# M240X.net
KiCad netlist of a schematic drawn in EAGLE
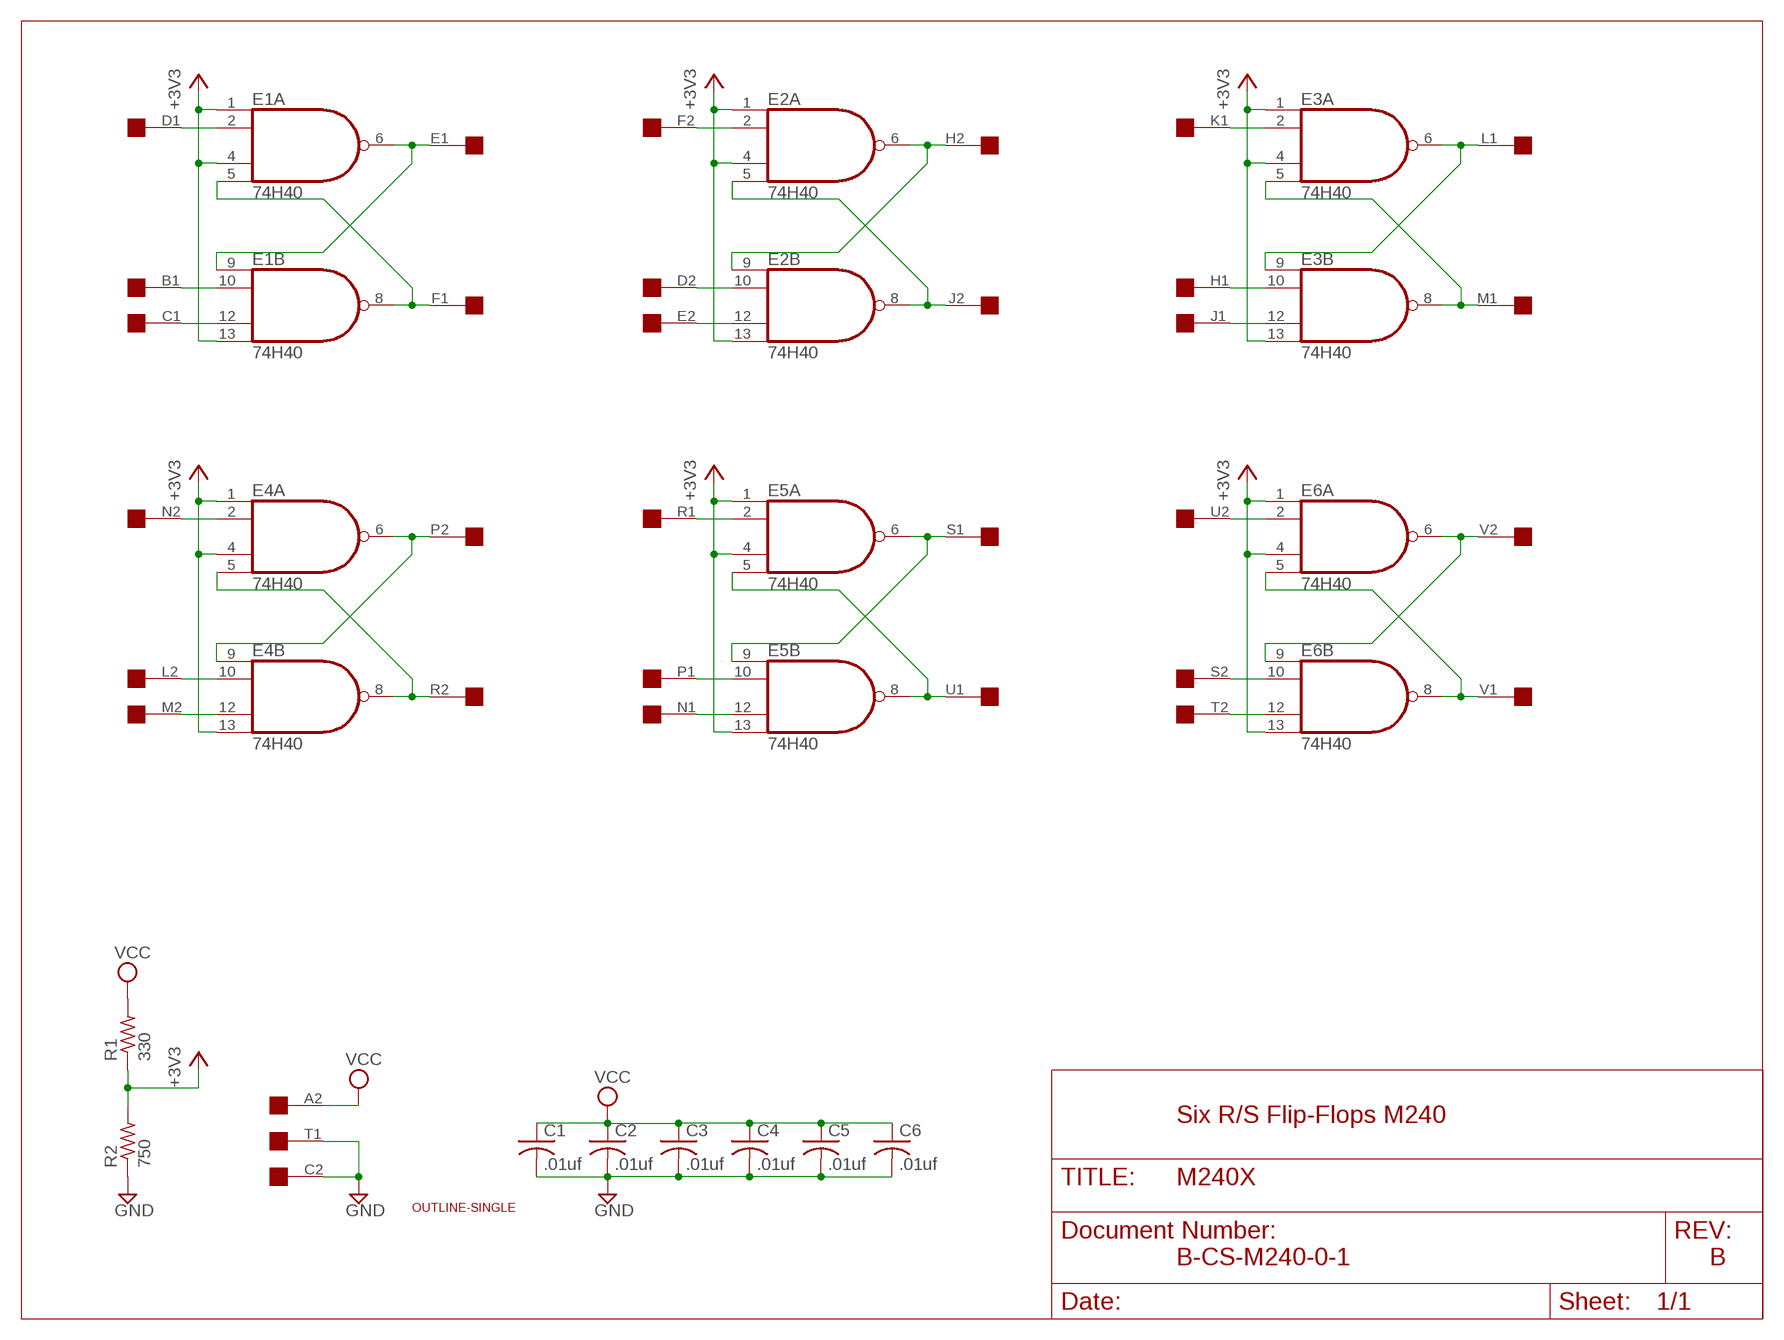
[diagram p0: schematic, sheet 1]

(export (version "E")
  (design (tool "Eeschema 10.0.6"))
  (components
    (comp (ref "C1")
      (value ".01uf")
      (footprint "eagle-import:C050-025X075")
      (libsource (lib "eagle-import") (part "C-US050-025X075"))
    )
    (comp (ref "C2")
      (value ".01uf")
      (footprint "eagle-import:C050-025X075")
      (libsource (lib "eagle-import") (part "C-US050-025X075"))
    )
    (comp (ref "C3")
      (value ".01uf")
      (footprint "eagle-import:C050-025X075")
      (libsource (lib "eagle-import") (part "C-US050-025X075"))
    )
    (comp (ref "C4")
      (value ".01uf")
      (footprint "eagle-import:C050-025X075")
      (libsource (lib "eagle-import") (part "C-US050-025X075"))
    )
    (comp (ref "C5")
      (value ".01uf")
      (footprint "eagle-import:C050-025X075")
      (libsource (lib "eagle-import") (part "C-US050-025X075"))
    )
    (comp (ref "C6")
      (value ".01uf")
      (footprint "eagle-import:C050-025X075")
      (libsource (lib "eagle-import") (part "C-US050-025X075"))
    )
    (comp (ref "E1")
      (value "74H40")
      (footprint "eagle-import:DIL14")
      (libsource (lib "eagle-import") (part "7420NS"))
    )
    (comp (ref "E2")
      (value "74H40")
      (footprint "eagle-import:DIL14")
      (libsource (lib "eagle-import") (part "7420NS"))
    )
    (comp (ref "E3")
      (value "74H40")
      (footprint "eagle-import:DIL14")
      (libsource (lib "eagle-import") (part "7420NS"))
    )
    (comp (ref "E4")
      (value "74H40")
      (footprint "eagle-import:DIL14")
      (libsource (lib "eagle-import") (part "7420NS"))
    )
    (comp (ref "E5")
      (value "74H40")
      (footprint "eagle-import:DIL14")
      (libsource (lib "eagle-import") (part "7420NS"))
    )
    (comp (ref "E6")
      (value "74H40")
      (footprint "eagle-import:DIL14")
      (libsource (lib "eagle-import") (part "7420NS"))
    )
    (comp (ref "R1")
      (value "330")
      (footprint "eagle-import:0207_10")
      (libsource (lib "eagle-import") (part "R-US_0207/10"))
    )
    (comp (ref "R2")
      (value "750")
      (footprint "eagle-import:0207_10")
      (libsource (lib "eagle-import") (part "R-US_0207/10"))
    )
    (comp (ref "U$1")
      (value "OUTLINE-SINGLE")
      (footprint "eagle-import:SINGLE")
      (libsource (lib "eagle-import") (part "OUTLINE-SINGLE"))
    )
    (comp (ref "U$4")
      (value "SINGLE")
      (footprint "eagle-import:EDGE-CON2")
      (libsource (lib "eagle-import") (part "SINGLE"))
    )
  )
  (nets
    (net (code "1") (name "+3V3") (class "Default")
      (node (ref "E1") (pin "1") (pinfunction "I0_1") (pintype "input"))
      (node (ref "E1") (pin "13") (pinfunction "I3_13") (pintype "input"))
      (node (ref "E1") (pin "4") (pinfunction "I2_4") (pintype "input"))
      (node (ref "E2") (pin "1") (pinfunction "I0_1") (pintype "input"))
      (node (ref "E2") (pin "13") (pinfunction "I3_13") (pintype "input"))
      (node (ref "E2") (pin "4") (pinfunction "I2_4") (pintype "input"))
      (node (ref "E3") (pin "1") (pinfunction "I0_1") (pintype "input"))
      (node (ref "E3") (pin "13") (pinfunction "I3_13") (pintype "input"))
      (node (ref "E3") (pin "4") (pinfunction "I2_4") (pintype "input"))
      (node (ref "E4") (pin "1") (pinfunction "I0_1") (pintype "input"))
      (node (ref "E4") (pin "13") (pinfunction "I3_13") (pintype "input"))
      (node (ref "E4") (pin "4") (pinfunction "I2_4") (pintype "input"))
      (node (ref "E5") (pin "1") (pinfunction "I0_1") (pintype "input"))
      (node (ref "E5") (pin "13") (pinfunction "I3_13") (pintype "input"))
      (node (ref "E5") (pin "4") (pinfunction "I2_4") (pintype "input"))
      (node (ref "E6") (pin "1") (pinfunction "I0_1") (pintype "input"))
      (node (ref "E6") (pin "13") (pinfunction "I3_13") (pintype "input"))
      (node (ref "E6") (pin "4") (pinfunction "I2_4") (pintype "input"))
      (node (ref "R1") (pin "1") (pinfunction "1_1") (pintype "passive"))
      (node (ref "R2") (pin "2") (pinfunction "2_2") (pintype "passive"))
    )
    (net (code "2") (name "GND") (class "Default")
      (node (ref "C1") (pin "2") (pinfunction "2_2") (pintype "passive"))
      (node (ref "C2") (pin "2") (pinfunction "2_2") (pintype "passive"))
      (node (ref "C3") (pin "2") (pinfunction "2_2") (pintype "passive"))
      (node (ref "C4") (pin "2") (pinfunction "2_2") (pintype "passive"))
      (node (ref "C5") (pin "2") (pinfunction "2_2") (pintype "passive"))
      (node (ref "C6") (pin "2") (pinfunction "2_2") (pintype "passive"))
      (node (ref "R2") (pin "1") (pinfunction "1_1") (pintype "passive"))
      (node (ref "U$4") (pin "C2") (pinfunction "1_C2") (pintype "bidirectional"))
      (node (ref "U$4") (pin "T1") (pinfunction "1_T1") (pintype "bidirectional"))
    )
    (net (code "3") (name "Net-(E1A-I1)") (class "Default")
      (node (ref "E1") (pin "2") (pinfunction "I1_2") (pintype "input"))
      (node (ref "U$4") (pin "D1") (pinfunction "1_D1") (pintype "bidirectional"))
    )
    (net (code "4") (name "Net-(E1A-I3)") (class "Default")
      (node (ref "E1") (pin "5") (pinfunction "I3_5") (pintype "input"))
      (node (ref "E1") (pin "8") (pinfunction "O_8") (pintype "output"))
      (node (ref "U$4") (pin "F1") (pinfunction "1_F1") (pintype "bidirectional"))
    )
    (net (code "5") (name "Net-(E1A-O)") (class "Default")
      (node (ref "E1") (pin "6") (pinfunction "O_6") (pintype "output"))
      (node (ref "E1") (pin "9") (pinfunction "I0_9") (pintype "input"))
      (node (ref "U$4") (pin "E1") (pinfunction "1_E1") (pintype "bidirectional"))
    )
    (net (code "6") (name "Net-(E1B-I1)") (class "Default")
      (node (ref "E1") (pin "10") (pinfunction "I1_10") (pintype "input"))
      (node (ref "U$4") (pin "B1") (pinfunction "1_B1") (pintype "bidirectional"))
    )
    (net (code "7") (name "Net-(E1B-I2)") (class "Default")
      (node (ref "E1") (pin "12") (pinfunction "I2_12") (pintype "input"))
      (node (ref "U$4") (pin "C1") (pinfunction "1_C1") (pintype "bidirectional"))
    )
    (net (code "8") (name "Net-(E2A-I1)") (class "Default")
      (node (ref "E2") (pin "2") (pinfunction "I1_2") (pintype "input"))
      (node (ref "U$4") (pin "F2") (pinfunction "1_F2") (pintype "bidirectional"))
    )
    (net (code "9") (name "Net-(E2A-I3)") (class "Default")
      (node (ref "E2") (pin "5") (pinfunction "I3_5") (pintype "input"))
      (node (ref "E2") (pin "8") (pinfunction "O_8") (pintype "output"))
      (node (ref "U$4") (pin "J2") (pinfunction "1_J2") (pintype "bidirectional"))
    )
    (net (code "10") (name "Net-(E2A-O)") (class "Default")
      (node (ref "E2") (pin "6") (pinfunction "O_6") (pintype "output"))
      (node (ref "E2") (pin "9") (pinfunction "I0_9") (pintype "input"))
      (node (ref "U$4") (pin "H2") (pinfunction "1_H2") (pintype "bidirectional"))
    )
    (net (code "11") (name "Net-(E2B-I1)") (class "Default")
      (node (ref "E2") (pin "10") (pinfunction "I1_10") (pintype "input"))
      (node (ref "U$4") (pin "D2") (pinfunction "1_D2") (pintype "bidirectional"))
    )
    (net (code "12") (name "Net-(E2B-I2)") (class "Default")
      (node (ref "E2") (pin "12") (pinfunction "I2_12") (pintype "input"))
      (node (ref "U$4") (pin "E2") (pinfunction "1_E2") (pintype "bidirectional"))
    )
    (net (code "13") (name "Net-(E3A-I1)") (class "Default")
      (node (ref "E3") (pin "2") (pinfunction "I1_2") (pintype "input"))
      (node (ref "U$4") (pin "K1") (pinfunction "1_K1") (pintype "bidirectional"))
    )
    (net (code "14") (name "Net-(E3A-I3)") (class "Default")
      (node (ref "E3") (pin "5") (pinfunction "I3_5") (pintype "input"))
      (node (ref "E3") (pin "8") (pinfunction "O_8") (pintype "output"))
      (node (ref "U$4") (pin "M1") (pinfunction "1_M1") (pintype "bidirectional"))
    )
    (net (code "15") (name "Net-(E3A-O)") (class "Default")
      (node (ref "E3") (pin "6") (pinfunction "O_6") (pintype "output"))
      (node (ref "E3") (pin "9") (pinfunction "I0_9") (pintype "input"))
      (node (ref "U$4") (pin "L1") (pinfunction "1_L1") (pintype "bidirectional"))
    )
    (net (code "16") (name "Net-(E3B-I1)") (class "Default")
      (node (ref "E3") (pin "10") (pinfunction "I1_10") (pintype "input"))
      (node (ref "U$4") (pin "H1") (pinfunction "1_H1") (pintype "bidirectional"))
    )
    (net (code "17") (name "Net-(E3B-I2)") (class "Default")
      (node (ref "E3") (pin "12") (pinfunction "I2_12") (pintype "input"))
      (node (ref "U$4") (pin "J1") (pinfunction "1_J1") (pintype "bidirectional"))
    )
    (net (code "18") (name "Net-(E4A-I1)") (class "Default")
      (node (ref "E4") (pin "2") (pinfunction "I1_2") (pintype "input"))
      (node (ref "U$4") (pin "N2") (pinfunction "1_N2") (pintype "bidirectional"))
    )
    (net (code "19") (name "Net-(E4A-I3)") (class "Default")
      (node (ref "E4") (pin "5") (pinfunction "I3_5") (pintype "input"))
      (node (ref "E4") (pin "8") (pinfunction "O_8") (pintype "output"))
      (node (ref "U$4") (pin "R2") (pinfunction "1_R2") (pintype "bidirectional"))
    )
    (net (code "20") (name "Net-(E4A-O)") (class "Default")
      (node (ref "E4") (pin "6") (pinfunction "O_6") (pintype "output"))
      (node (ref "E4") (pin "9") (pinfunction "I0_9") (pintype "input"))
      (node (ref "U$4") (pin "P2") (pinfunction "1_P2") (pintype "bidirectional"))
    )
    (net (code "21") (name "Net-(E4B-I1)") (class "Default")
      (node (ref "E4") (pin "10") (pinfunction "I1_10") (pintype "input"))
      (node (ref "U$4") (pin "L2") (pinfunction "1_L2") (pintype "bidirectional"))
    )
    (net (code "22") (name "Net-(E4B-I2)") (class "Default")
      (node (ref "E4") (pin "12") (pinfunction "I2_12") (pintype "input"))
      (node (ref "U$4") (pin "M2") (pinfunction "1_M2") (pintype "bidirectional"))
    )
    (net (code "23") (name "Net-(E5A-I1)") (class "Default")
      (node (ref "E5") (pin "2") (pinfunction "I1_2") (pintype "input"))
      (node (ref "U$4") (pin "R1") (pinfunction "1_R1") (pintype "bidirectional"))
    )
    (net (code "24") (name "Net-(E5A-I3)") (class "Default")
      (node (ref "E5") (pin "5") (pinfunction "I3_5") (pintype "input"))
      (node (ref "E5") (pin "8") (pinfunction "O_8") (pintype "output"))
      (node (ref "U$4") (pin "U1") (pinfunction "1_U1") (pintype "bidirectional"))
    )
    (net (code "25") (name "Net-(E5A-O)") (class "Default")
      (node (ref "E5") (pin "6") (pinfunction "O_6") (pintype "output"))
      (node (ref "E5") (pin "9") (pinfunction "I0_9") (pintype "input"))
      (node (ref "U$4") (pin "S1") (pinfunction "1_S1") (pintype "bidirectional"))
    )
    (net (code "26") (name "Net-(E5B-I1)") (class "Default")
      (node (ref "E5") (pin "10") (pinfunction "I1_10") (pintype "input"))
      (node (ref "U$4") (pin "P1") (pinfunction "1_P1") (pintype "bidirectional"))
    )
    (net (code "27") (name "Net-(E5B-I2)") (class "Default")
      (node (ref "E5") (pin "12") (pinfunction "I2_12") (pintype "input"))
      (node (ref "U$4") (pin "N1") (pinfunction "1_N1") (pintype "bidirectional"))
    )
    (net (code "28") (name "Net-(E6A-I1)") (class "Default")
      (node (ref "E6") (pin "2") (pinfunction "I1_2") (pintype "input"))
      (node (ref "U$4") (pin "U2") (pinfunction "1_U2") (pintype "bidirectional"))
    )
    (net (code "29") (name "Net-(E6A-I3)") (class "Default")
      (node (ref "E6") (pin "5") (pinfunction "I3_5") (pintype "input"))
      (node (ref "E6") (pin "8") (pinfunction "O_8") (pintype "output"))
      (node (ref "U$4") (pin "V1") (pinfunction "1_V1") (pintype "bidirectional"))
    )
    (net (code "30") (name "Net-(E6A-O)") (class "Default")
      (node (ref "E6") (pin "6") (pinfunction "O_6") (pintype "output"))
      (node (ref "E6") (pin "9") (pinfunction "I0_9") (pintype "input"))
      (node (ref "U$4") (pin "V2") (pinfunction "1_V2") (pintype "bidirectional"))
    )
    (net (code "31") (name "Net-(E6B-I1)") (class "Default")
      (node (ref "E6") (pin "10") (pinfunction "I1_10") (pintype "input"))
      (node (ref "U$4") (pin "S2") (pinfunction "1_S2") (pintype "bidirectional"))
    )
    (net (code "32") (name "Net-(E6B-I2)") (class "Default")
      (node (ref "E6") (pin "12") (pinfunction "I2_12") (pintype "input"))
      (node (ref "U$4") (pin "T2") (pinfunction "1_T2") (pintype "bidirectional"))
    )
    (net (code "33") (name "VCC") (class "Default")
      (node (ref "C1") (pin "1") (pinfunction "1_1") (pintype "passive"))
      (node (ref "C2") (pin "1") (pinfunction "1_1") (pintype "passive"))
      (node (ref "C3") (pin "1") (pinfunction "1_1") (pintype "passive"))
      (node (ref "C4") (pin "1") (pinfunction "1_1") (pintype "passive"))
      (node (ref "C5") (pin "1") (pinfunction "1_1") (pintype "passive"))
      (node (ref "C6") (pin "1") (pinfunction "1_1") (pintype "passive"))
      (node (ref "R1") (pin "2") (pinfunction "2_2") (pintype "passive"))
      (node (ref "U$4") (pin "A2") (pinfunction "1_A2") (pintype "bidirectional"))
    )
  )
)
